# MotorController.net
KiCad netlist of a schematic drawn in Altium Designer
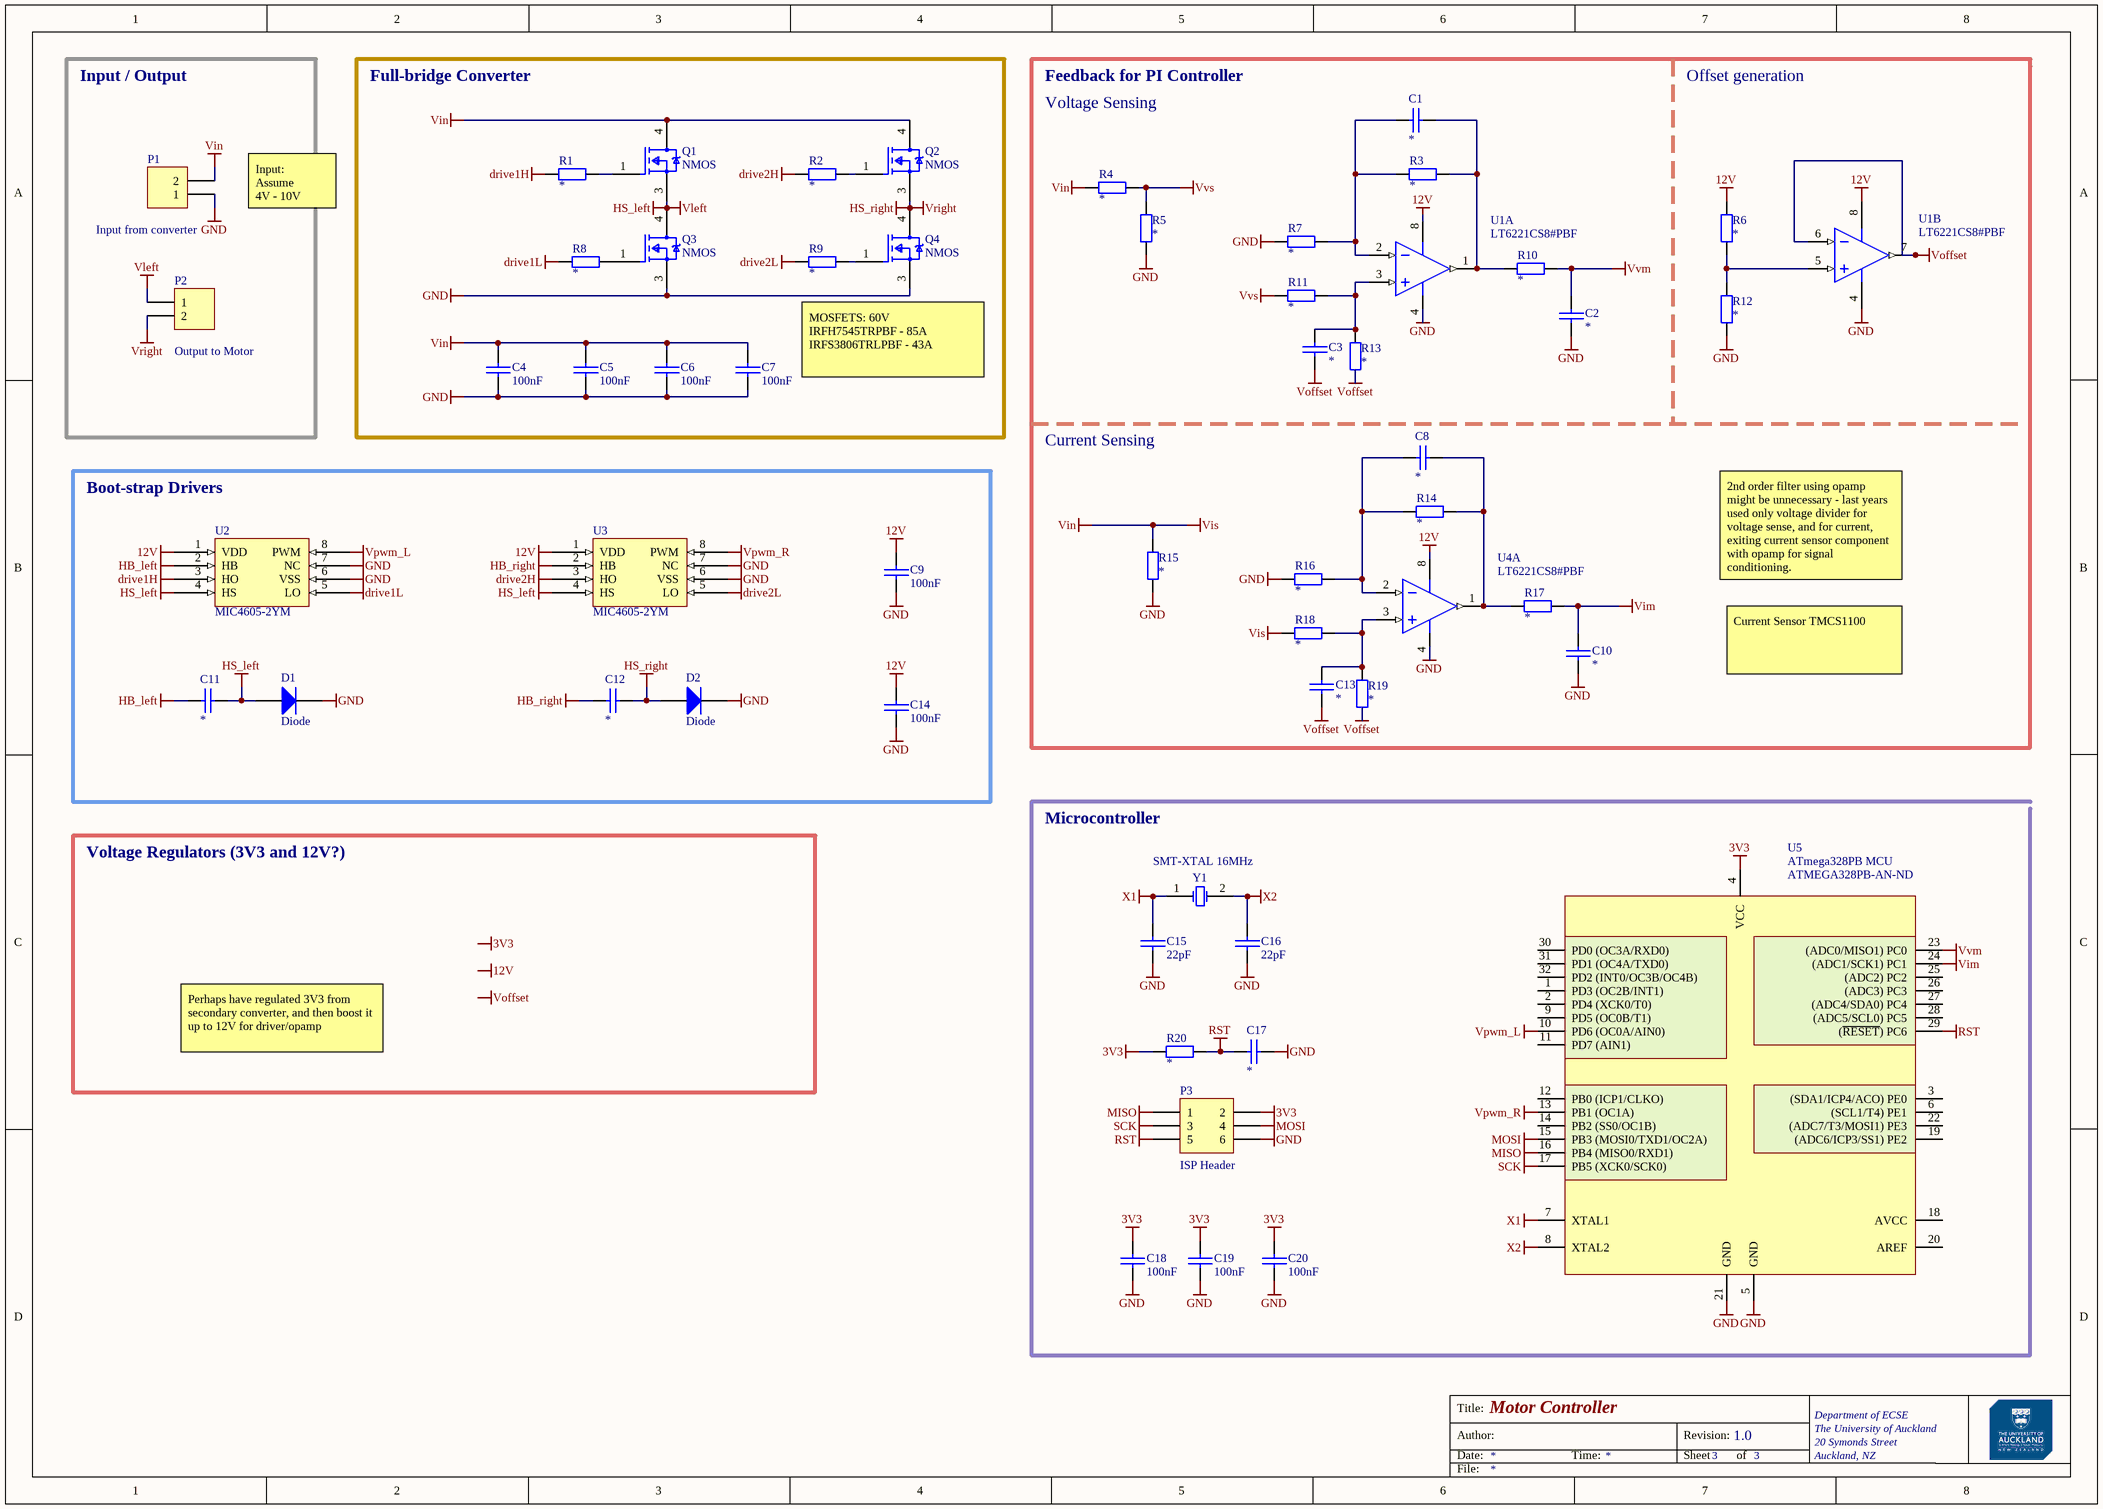
[diagram p0: MotorController.SchDoc]

(export (version "E")
  (design (tool "Eeschema 10.0.6"))
  (components
    (comp (ref "C1")
      (value "*")
      (footprint "0805 CAP")
      (description "SMT ceramic capacitor 0805 size")
      (libsource (lib "EE209_Library") (part "CerCap_SMT_0805"))
    )
    (comp (ref "C2")
      (value "*")
      (footprint "0805 CAP")
      (description "SMT ceramic capacitor 0805 size")
      (libsource (lib "EE209_Library") (part "CerCap_SMT_0805"))
    )
    (comp (ref "C3")
      (value "*")
      (footprint "0805 CAP")
      (description "SMT ceramic capacitor 0805 size")
      (libsource (lib "EE209_Library") (part "CerCap_SMT_0805"))
    )
    (comp (ref "C4")
      (value "100nF")
      (footprint "0805 CAP")
      (description "SMT ceramic capacitor 0805 size")
      (libsource (lib "EE209_Library") (part "CerCap_SMT_0805"))
    )
    (comp (ref "C5")
      (value "100nF")
      (footprint "0805 CAP")
      (description "SMT ceramic capacitor 0805 size")
      (libsource (lib "EE209_Library") (part "CerCap_SMT_0805"))
    )
    (comp (ref "C6")
      (value "100nF")
      (footprint "0805 CAP")
      (description "SMT ceramic capacitor 0805 size")
      (libsource (lib "EE209_Library") (part "CerCap_SMT_0805"))
    )
    (comp (ref "C7")
      (value "100nF")
      (footprint "0805 CAP")
      (description "SMT ceramic capacitor 0805 size")
      (libsource (lib "EE209_Library") (part "CerCap_SMT_0805"))
    )
    (comp (ref "C8")
      (value "*")
      (footprint "0805 CAP")
      (description "SMT ceramic capacitor 0805 size")
      (libsource (lib "EE209_Library") (part "CerCap_SMT_0805"))
    )
    (comp (ref "C9")
      (value "100nF")
      (footprint "0805 CAP")
      (description "SMT ceramic capacitor 0805 size")
      (libsource (lib "EE209_Library") (part "CerCap_SMT_0805"))
    )
    (comp (ref "C10")
      (value "*")
      (footprint "0805 CAP")
      (description "SMT ceramic capacitor 0805 size")
      (libsource (lib "EE209_Library") (part "CerCap_SMT_0805"))
    )
    (comp (ref "C11")
      (value "*")
      (footprint "0805 CAP")
      (description "SMT ceramic capacitor 0805 size")
      (libsource (lib "EE209_Library") (part "CerCap_SMT_0805"))
    )
    (comp (ref "C12")
      (value "*")
      (footprint "0805 CAP")
      (description "SMT ceramic capacitor 0805 size")
      (libsource (lib "EE209_Library") (part "CerCap_SMT_0805"))
    )
    (comp (ref "C13")
      (value "*")
      (footprint "0805 CAP")
      (description "SMT ceramic capacitor 0805 size")
      (libsource (lib "EE209_Library") (part "CerCap_SMT_0805"))
    )
    (comp (ref "C14")
      (value "100nF")
      (footprint "0805 CAP")
      (description "SMT ceramic capacitor 0805 size")
      (libsource (lib "EE209_Library") (part "CerCap_SMT_0805"))
    )
    (comp (ref "C15")
      (value "22pF")
      (footprint "0805 CAP")
      (description "SMT ceramic capacitor 0805 size")
      (libsource (lib "EE209_Library") (part "CerCap_SMT_0805"))
    )
    (comp (ref "C16")
      (value "22pF")
      (footprint "0805 CAP")
      (description "SMT ceramic capacitor 0805 size")
      (libsource (lib "EE209_Library") (part "CerCap_SMT_0805"))
    )
    (comp (ref "C17")
      (value "*")
      (footprint "0805 CAP")
      (description "SMT ceramic capacitor 0805 size")
      (libsource (lib "EE209_Library") (part "CerCap_SMT_0805"))
    )
    (comp (ref "C18")
      (value "100nF")
      (footprint "0805 CAP")
      (description "SMT ceramic capacitor 0805 size")
      (libsource (lib "EE209_Library") (part "CerCap_SMT_0805"))
    )
    (comp (ref "C19")
      (value "100nF")
      (footprint "0805 CAP")
      (description "SMT ceramic capacitor 0805 size")
      (libsource (lib "EE209_Library") (part "CerCap_SMT_0805"))
    )
    (comp (ref "C20")
      (value "100nF")
      (footprint "0805 CAP")
      (description "SMT ceramic capacitor 0805 size")
      (libsource (lib "EE209_Library") (part "CerCap_SMT_0805"))
    )
    (comp (ref "D1")
      (value "Diode")
      (footprint "SMC")
      (description "Default Diode")
      (fields (field (name "PUBLISHER") "Altium Limited"))
      (libsource (lib "Miscellaneous Devices") (part "Diode"))
    )
    (comp (ref "D2")
      (value "Diode")
      (footprint "SMC")
      (description "Default Diode")
      (fields (field (name "PUBLISHER") "Altium Limited"))
      (libsource (lib "Miscellaneous Devices") (part "Diode"))
    )
    (comp (ref "P1")
      (value "Input from converter")
      (footprint "HDR1X2H")
      (description "Header, 2-Pin, Right Angle")
      (fields (field (name "PUBLISHER") "Altium Limited"))
      (libsource (lib "") (part "Header 2H_1"))
    )
    (comp (ref "P2")
      (value "Output to Motor")
      (footprint "HDR1X2H")
      (description "Header, 2-Pin, Right Angle")
      (fields (field (name "PUBLISHER") "Altium Limited"))
      (libsource (lib "Miscellaneous Connectors") (part "Header 2H"))
    )
    (comp (ref "P3")
      (value "ISP Header")
      (footprint "HDR2X3")
      (description "Header, 3-Pin, Dual row")
      (fields (field (name "PUBLISHER") "Altium Limited"))
      (libsource (lib "Miscellaneous Connectors") (part "Header 3X2"))
    )
    (comp (ref "Q1")
      (value "NMOS")
      (footprint "IRFS3806TRLPBFCT-ND")
      (description "Single N-Channel 60V 15.8 mOhm 22 nC HEXFET® Power Mosfet - D2PAK")
      (fields
        (field (name "MANUFACTURER") "Infineon")
        (field (name "MANUFACTURER PART NUMBER") "IRFS3806TRLPBF")
      )
      (libsource (lib "SummerWorkshop") (part "NMOS"))
    )
    (comp (ref "Q2")
      (value "NMOS")
      (footprint "IRFS3806TRLPBFCT-ND")
      (description "Single N-Channel 60V 15.8 mOhm 22 nC HEXFET® Power Mosfet - D2PAK")
      (fields
        (field (name "MANUFACTURER") "Infineon")
        (field (name "MANUFACTURER PART NUMBER") "IRFS3806TRLPBF")
      )
      (libsource (lib "SummerWorkshop") (part "NMOS"))
    )
    (comp (ref "Q3")
      (value "NMOS")
      (footprint "IRFS3806TRLPBFCT-ND")
      (description "Single N-Channel 60V 15.8 mOhm 22 nC HEXFET® Power Mosfet - D2PAK")
      (fields
        (field (name "MANUFACTURER") "Infineon")
        (field (name "MANUFACTURER PART NUMBER") "IRFS3806TRLPBF")
      )
      (libsource (lib "SummerWorkshop") (part "NMOS"))
    )
    (comp (ref "Q4")
      (value "NMOS")
      (footprint "IRFS3806TRLPBFCT-ND")
      (description "Single N-Channel 60V 15.8 mOhm 22 nC HEXFET® Power Mosfet - D2PAK")
      (fields
        (field (name "MANUFACTURER") "Infineon")
        (field (name "MANUFACTURER PART NUMBER") "IRFS3806TRLPBF")
      )
      (libsource (lib "SummerWorkshop") (part "NMOS"))
    )
    (comp (ref "R1")
      (value "*")
      (footprint "0805 RES")
      (description "0805 resistor")
      (fields (field (name "PUBLISHER") "Altium Limited"))
      (libsource (lib "EE209_Library") (part "Res_SMT_0805"))
    )
    (comp (ref "R2")
      (value "*")
      (footprint "0805 RES")
      (description "0805 resistor")
      (fields (field (name "PUBLISHER") "Altium Limited"))
      (libsource (lib "EE209_Library") (part "Res_SMT_0805"))
    )
    (comp (ref "R3")
      (value "*")
      (footprint "0805 RES")
      (description "0805 resistor")
      (fields (field (name "PUBLISHER") "Altium Limited"))
      (libsource (lib "") (part "Res_SMT_0805_2"))
    )
    (comp (ref "R4")
      (value "*")
      (footprint "0805 RES")
      (description "0805 resistor")
      (fields (field (name "PUBLISHER") "Altium Limited"))
      (libsource (lib "") (part "Res_SMT_0805_2"))
    )
    (comp (ref "R5")
      (value "*")
      (footprint "0805 RES")
      (description "0805 resistor")
      (fields (field (name "PUBLISHER") "Altium Limited"))
      (libsource (lib "") (part "Res_SMT_0805_3"))
    )
    (comp (ref "R6")
      (value "*")
      (footprint "0805 RES")
      (description "0805 resistor")
      (fields (field (name "PUBLISHER") "Altium Limited"))
      (libsource (lib "") (part "Res_SMT_0805_1"))
    )
    (comp (ref "R7")
      (value "*")
      (footprint "0805 RES")
      (description "0805 resistor")
      (fields (field (name "PUBLISHER") "Altium Limited"))
      (libsource (lib "EE209_Library") (part "Res_SMT_0805"))
    )
    (comp (ref "R8")
      (value "*")
      (footprint "0805 RES")
      (description "0805 resistor")
      (fields (field (name "PUBLISHER") "Altium Limited"))
      (libsource (lib "EE209_Library") (part "Res_SMT_0805"))
    )
    (comp (ref "R9")
      (value "*")
      (footprint "0805 RES")
      (description "0805 resistor")
      (fields (field (name "PUBLISHER") "Altium Limited"))
      (libsource (lib "EE209_Library") (part "Res_SMT_0805"))
    )
    (comp (ref "R10")
      (value "*")
      (footprint "0805 RES")
      (description "0805 resistor")
      (fields (field (name "PUBLISHER") "Altium Limited"))
      (libsource (lib "") (part "Res_SMT_0805_2"))
    )
    (comp (ref "R11")
      (value "*")
      (footprint "0805 RES")
      (description "0805 resistor")
      (fields (field (name "PUBLISHER") "Altium Limited"))
      (libsource (lib "EE209_Library") (part "Res_SMT_0805"))
    )
    (comp (ref "R12")
      (value "*")
      (footprint "0805 RES")
      (description "0805 resistor")
      (fields (field (name "PUBLISHER") "Altium Limited"))
      (libsource (lib "") (part "Res_SMT_0805_1"))
    )
    (comp (ref "R13")
      (value "*")
      (footprint "0805 RES")
      (description "0805 resistor")
      (fields (field (name "PUBLISHER") "Altium Limited"))
      (libsource (lib "") (part "Res_SMT_0805_1"))
    )
    (comp (ref "R14")
      (value "*")
      (footprint "0805 RES")
      (description "0805 resistor")
      (fields (field (name "PUBLISHER") "Altium Limited"))
      (libsource (lib "") (part "Res_SMT_0805_2"))
    )
    (comp (ref "R15")
      (value "*")
      (footprint "0805 RES")
      (description "0805 resistor")
      (fields (field (name "PUBLISHER") "Altium Limited"))
      (libsource (lib "") (part "Res_SMT_0805_3"))
    )
    (comp (ref "R16")
      (value "*")
      (footprint "0805 RES")
      (description "0805 resistor")
      (fields (field (name "PUBLISHER") "Altium Limited"))
      (libsource (lib "EE209_Library") (part "Res_SMT_0805"))
    )
    (comp (ref "R17")
      (value "*")
      (footprint "0805 RES")
      (description "0805 resistor")
      (fields (field (name "PUBLISHER") "Altium Limited"))
      (libsource (lib "") (part "Res_SMT_0805_2"))
    )
    (comp (ref "R18")
      (value "*")
      (footprint "0805 RES")
      (description "0805 resistor")
      (fields (field (name "PUBLISHER") "Altium Limited"))
      (libsource (lib "EE209_Library") (part "Res_SMT_0805"))
    )
    (comp (ref "R19")
      (value "*")
      (footprint "0805 RES")
      (description "0805 resistor")
      (fields (field (name "PUBLISHER") "Altium Limited"))
      (libsource (lib "") (part "Res_SMT_0805_1"))
    )
    (comp (ref "R20")
      (value "*")
      (footprint "0805 RES")
      (description "0805 resistor")
      (fields (field (name "PUBLISHER") "Altium Limited"))
      (libsource (lib "") (part "Res_SMT_0805_2"))
    )
    (comp (ref "U1")
      (value "LT6221CS8#PBF")
      (footprint "LT-S8-8_N")
      (fields
        (field (name "LINEAR TECHNOLOGY PART NUMBER") "LT6221")
        (field (name "MANUFACTURER") "Linear Technology")
      )
      (libsource (lib "Altium Content Vault") (part "LT-LT6221-S8-8"))
    )
    (comp (ref "U2")
      (value "MIC4605-2YM")
      (description "Driver 1A 2-OUT High and Low Side Half Brdg Non-Inv 8-Pin SOIC N Tube")
      (fields
        (field (name "MANUFACTURER") "Microchip")
        (field (name "MANUFACTURER PART NUMBER") "MIC4605-2YM-T5")
      )
      (libsource (lib "SummerWorkshop") (part "MIC4605-2YM"))
    )
    (comp (ref "U3")
      (value "MIC4605-2YM")
      (description "Driver 1A 2-OUT High and Low Side Half Brdg Non-Inv 8-Pin SOIC N Tube")
      (fields
        (field (name "MANUFACTURER") "Microchip")
        (field (name "MANUFACTURER PART NUMBER") "MIC4605-2YM-T5")
      )
      (libsource (lib "SummerWorkshop") (part "MIC4605-2YM"))
    )
    (comp (ref "U4")
      (value "LT6221CS8#PBF")
      (footprint "LT-S8-8_N")
      (fields
        (field (name "LINEAR TECHNOLOGY PART NUMBER") "LT6221")
        (field (name "MANUFACTURER") "Linear Technology")
      )
      (libsource (lib "Altium Content Vault") (part "LT-LT6221-S8-8"))
    )
    (comp (ref "U5")
      (value "ATmega328PB MCU")
      (footprint "32 - TQFP")
      (description "IC MCU 8BIT 32KB FLASH 32TQFP")
      (fields
        (field (name "MANUFACTURER") "Atmel")
        (field (name "MANUFACTURER PART NUMBER") "ATMEGA328PB-AN")
        (field (name "SUPPLIER PART NUMBER 1") "ATMEGA328PB-AN-ND")
      )
      (libsource (lib "EE209_Library") (part "ATmega328PB_SMT_TQFP32"))
    )
    (comp (ref "Y1")
      (value "SMT-XTAL 16MHz")
      (footprint "HC49-US")
      (description "9C-16.000MAAJ-T crystal 16.0000MHZ 18PF SMD")
      (fields
        (field (name "MANUFACTURER") "TXC CORPORATION")
        (field (name "MANUFACTURER PART NUMBER") "9C-16.000MAAJ-T")
      )
      (libsource (lib "EE209_Library") (part "TXC9C-16_XTAL_SMT"))
    )
  )
  (nets
    (net (code "1") (name "3V3") (class "Default")
      (node (ref "C18") (pin "1") (pinfunction "1_1") (pintype "passive"))
      (node (ref "C19") (pin "1") (pinfunction "1_1") (pintype "passive"))
      (node (ref "C20") (pin "1") (pinfunction "1_1") (pintype "passive"))
      (node (ref "P3") (pin "2") (pinfunction "2_2") (pintype "passive"))
      (node (ref "R20") (pin "2") (pinfunction "2_2") (pintype "passive"))
      (node (ref "U5") (pin "4") (pinfunction "VCC_4") (pintype "passive"))
    )
    (net (code "2") (name "12V") (class "Default")
      (node (ref "C14") (pin "2") (pinfunction "2_2") (pintype "passive"))
      (node (ref "C9") (pin "2") (pinfunction "2_2") (pintype "passive"))
      (node (ref "R6") (pin "2") (pinfunction "2_2") (pintype "passive"))
      (node (ref "U1") (pin "8") (pinfunction "VS+_8") (pintype "power_in"))
      (node (ref "U2") (pin "1") (pinfunction "VDD_1") (pintype "input"))
      (node (ref "U3") (pin "1") (pinfunction "VDD_1") (pintype "input"))
      (node (ref "U4") (pin "8") (pinfunction "VS+_8") (pintype "power_in"))
    )
    (net (code "3") (name "GND") (class "Default")
      (node (ref "C10") (pin "1") (pinfunction "1_1") (pintype "passive"))
      (node (ref "C14") (pin "1") (pinfunction "1_1") (pintype "passive"))
      (node (ref "C15") (pin "2") (pinfunction "2_2") (pintype "passive"))
      (node (ref "C16") (pin "2") (pinfunction "2_2") (pintype "passive"))
      (node (ref "C17") (pin "2") (pinfunction "2_2") (pintype "passive"))
      (node (ref "C18") (pin "2") (pinfunction "2_2") (pintype "passive"))
      (node (ref "C19") (pin "2") (pinfunction "2_2") (pintype "passive"))
      (node (ref "C2") (pin "1") (pinfunction "1_1") (pintype "passive"))
      (node (ref "C20") (pin "2") (pinfunction "2_2") (pintype "passive"))
      (node (ref "C4") (pin "1") (pinfunction "1_1") (pintype "passive"))
      (node (ref "C5") (pin "1") (pinfunction "1_1") (pintype "passive"))
      (node (ref "C6") (pin "1") (pinfunction "1_1") (pintype "passive"))
      (node (ref "C7") (pin "1") (pinfunction "1_1") (pintype "passive"))
      (node (ref "C9") (pin "1") (pinfunction "1_1") (pintype "passive"))
      (node (ref "D1") (pin "2") (pinfunction "K_2") (pintype "passive"))
      (node (ref "D2") (pin "2") (pinfunction "K_2") (pintype "passive"))
      (node (ref "P1") (pin "1") (pinfunction "1_1") (pintype "passive"))
      (node (ref "P3") (pin "6") (pinfunction "6_6") (pintype "passive"))
      (node (ref "Q3") (pin "3") (pinfunction "S_3") (pintype "passive"))
      (node (ref "Q4") (pin "3") (pinfunction "S_3") (pintype "passive"))
      (node (ref "R12") (pin "1") (pinfunction "1_1") (pintype "passive"))
      (node (ref "R15") (pin "2") (pinfunction "2_2") (pintype "passive"))
      (node (ref "R16") (pin "1") (pinfunction "1_1") (pintype "passive"))
      (node (ref "R5") (pin "2") (pinfunction "2_2") (pintype "passive"))
      (node (ref "R7") (pin "1") (pinfunction "1_1") (pintype "passive"))
      (node (ref "U1") (pin "4") (pinfunction "VS-_4") (pintype "power_in"))
      (node (ref "U2") (pin "6") (pinfunction "VSS_6") (pintype "input"))
      (node (ref "U2") (pin "7") (pinfunction "NC_7") (pintype "input"))
      (node (ref "U3") (pin "6") (pinfunction "VSS_6") (pintype "input"))
      (node (ref "U3") (pin "7") (pinfunction "NC_7") (pintype "input"))
      (node (ref "U4") (pin "4") (pinfunction "VS-_4") (pintype "power_in"))
      (node (ref "U5") (pin "21") (pinfunction "GND_21") (pintype "passive"))
      (node (ref "U5") (pin "5") (pinfunction "GND_5") (pintype "passive"))
    )
    (net (code "4") (name "HB_left") (class "Default")
      (node (ref "C11") (pin "1") (pinfunction "1_1") (pintype "passive"))
      (node (ref "U2") (pin "2") (pinfunction "HB_2") (pintype "input"))
    )
    (net (code "5") (name "HB_right") (class "Default")
      (node (ref "C12") (pin "1") (pinfunction "1_1") (pintype "passive"))
      (node (ref "U3") (pin "2") (pinfunction "HB_2") (pintype "input"))
    )
    (net (code "6") (name "HS_left") (class "Default")
      (node (ref "C11") (pin "2") (pinfunction "2_2") (pintype "passive"))
      (node (ref "D1") (pin "1") (pinfunction "A_1") (pintype "passive"))
      (node (ref "P2") (pin "1") (pinfunction "1_1") (pintype "passive"))
      (node (ref "Q1") (pin "3") (pinfunction "S_3") (pintype "passive"))
      (node (ref "Q3") (pin "4") (pinfunction "D_4") (pintype "passive"))
      (node (ref "U2") (pin "4") (pinfunction "HS_4") (pintype "input"))
      (node (ref "U3") (pin "4") (pinfunction "HS_4") (pintype "input"))
    )
    (net (code "7") (name "HS_right") (class "Default")
      (node (ref "C12") (pin "2") (pinfunction "2_2") (pintype "passive"))
      (node (ref "D2") (pin "1") (pinfunction "A_1") (pintype "passive"))
      (node (ref "P2") (pin "2") (pinfunction "2_2") (pintype "passive"))
      (node (ref "Q2") (pin "3") (pinfunction "S_3") (pintype "passive"))
      (node (ref "Q4") (pin "4") (pinfunction "D_4") (pintype "passive"))
    )
    (net (code "8") (name "MISO") (class "Default")
      (node (ref "P3") (pin "1") (pinfunction "1_1") (pintype "passive"))
      (node (ref "U5") (pin "16") (pinfunction "PB4_(MISO0/RXD1)_16") (pintype "passive"))
    )
    (net (code "9") (name "MOSI") (class "Default")
      (node (ref "P3") (pin "4") (pinfunction "4_4") (pintype "passive"))
      (node (ref "U5") (pin "15") (pinfunction "PB3_(MOSI0/TXD1/OC2A)_15") (pintype "passive"))
    )
    (net (code "10") (name "Net-(Q1-G)") (class "Default")
      (node (ref "Q1") (pin "1") (pinfunction "G_1") (pintype "passive"))
      (node (ref "R1") (pin "2") (pinfunction "2_2") (pintype "passive"))
    )
    (net (code "11") (name "Net-(Q2-G)") (class "Default")
      (node (ref "Q2") (pin "1") (pinfunction "G_1") (pintype "passive"))
      (node (ref "R2") (pin "2") (pinfunction "2_2") (pintype "passive"))
    )
    (net (code "12") (name "Net-(Q3-G)") (class "Default")
      (node (ref "Q3") (pin "1") (pinfunction "G_1") (pintype "passive"))
      (node (ref "R8") (pin "2") (pinfunction "2_2") (pintype "passive"))
    )
    (net (code "13") (name "Net-(Q4-G)") (class "Default")
      (node (ref "Q4") (pin "1") (pinfunction "G_1") (pintype "passive"))
      (node (ref "R9") (pin "2") (pinfunction "2_2") (pintype "passive"))
    )
    (net (code "14") (name "Net-(U1A-+IN_A)") (class "Default")
      (node (ref "C3") (pin "2") (pinfunction "2_2") (pintype "passive"))
      (node (ref "R11") (pin "2") (pinfunction "2_2") (pintype "passive"))
      (node (ref "R13") (pin "2") (pinfunction "2_2") (pintype "passive"))
      (node (ref "U1") (pin "3") (pinfunction "+IN_A_3") (pintype "input"))
    )
    (net (code "15") (name "Net-(U1A--IN_A)") (class "Default")
      (node (ref "C1") (pin "1") (pinfunction "1_1") (pintype "passive"))
      (node (ref "R3") (pin "2") (pinfunction "2_2") (pintype "passive"))
      (node (ref "R7") (pin "2") (pinfunction "2_2") (pintype "passive"))
      (node (ref "U1") (pin "2") (pinfunction "-IN_A_2") (pintype "input"))
    )
    (net (code "16") (name "Net-(U1A-OUT_A)") (class "Default")
      (node (ref "C1") (pin "2") (pinfunction "2_2") (pintype "passive"))
      (node (ref "R10") (pin "2") (pinfunction "2_2") (pintype "passive"))
      (node (ref "R3") (pin "1") (pinfunction "1_1") (pintype "passive"))
      (node (ref "U1") (pin "1") (pinfunction "OUT_A_1") (pintype "output"))
    )
    (net (code "17") (name "Net-(U1B-+IN_B)") (class "Default")
      (node (ref "R12") (pin "2") (pinfunction "2_2") (pintype "passive"))
      (node (ref "R6") (pin "1") (pinfunction "1_1") (pintype "passive"))
      (node (ref "U1") (pin "5") (pinfunction "+IN_B_5") (pintype "input"))
    )
    (net (code "18") (name "Net-(U4A-+IN_A)") (class "Default")
      (node (ref "C13") (pin "2") (pinfunction "2_2") (pintype "passive"))
      (node (ref "R18") (pin "2") (pinfunction "2_2") (pintype "passive"))
      (node (ref "R19") (pin "2") (pinfunction "2_2") (pintype "passive"))
      (node (ref "U4") (pin "3") (pinfunction "+IN_A_3") (pintype "input"))
    )
    (net (code "19") (name "Net-(U4A--IN_A)") (class "Default")
      (node (ref "C8") (pin "1") (pinfunction "1_1") (pintype "passive"))
      (node (ref "R14") (pin "2") (pinfunction "2_2") (pintype "passive"))
      (node (ref "R16") (pin "2") (pinfunction "2_2") (pintype "passive"))
      (node (ref "U4") (pin "2") (pinfunction "-IN_A_2") (pintype "input"))
    )
    (net (code "20") (name "Net-(U4A-OUT_A)") (class "Default")
      (node (ref "C8") (pin "2") (pinfunction "2_2") (pintype "passive"))
      (node (ref "R14") (pin "1") (pinfunction "1_1") (pintype "passive"))
      (node (ref "R17") (pin "2") (pinfunction "2_2") (pintype "passive"))
      (node (ref "U4") (pin "1") (pinfunction "OUT_A_1") (pintype "output"))
    )
    (net (code "21") (name "RST") (class "Default")
      (node (ref "C17") (pin "1") (pinfunction "1_1") (pintype "passive"))
      (node (ref "P3") (pin "5") (pinfunction "5_5") (pintype "passive"))
      (node (ref "R20") (pin "1") (pinfunction "1_1") (pintype "passive"))
      (node (ref "U5") (pin "29") (pinfunction "(~{RESET})_PC6_29") (pintype "passive"))
    )
    (net (code "22") (name "SCK") (class "Default")
      (node (ref "P3") (pin "3") (pinfunction "3_3") (pintype "passive"))
      (node (ref "U5") (pin "17") (pinfunction "PB5_(XCK0/SCK0)_17") (pintype "passive"))
    )
    (net (code "23") (name "Vim") (class "Default")
      (node (ref "C10") (pin "2") (pinfunction "2_2") (pintype "passive"))
      (node (ref "R17") (pin "1") (pinfunction "1_1") (pintype "passive"))
      (node (ref "U5") (pin "24") (pinfunction "(ADC1/SCK1)_PC1_24") (pintype "passive"))
    )
    (net (code "24") (name "Vin") (class "Default")
      (node (ref "C4") (pin "2") (pinfunction "2_2") (pintype "passive"))
      (node (ref "C5") (pin "2") (pinfunction "2_2") (pintype "passive"))
      (node (ref "C6") (pin "2") (pinfunction "2_2") (pintype "passive"))
      (node (ref "C7") (pin "2") (pinfunction "2_2") (pintype "passive"))
      (node (ref "P1") (pin "2") (pinfunction "2_2") (pintype "passive"))
      (node (ref "Q1") (pin "4") (pinfunction "D_4") (pintype "passive"))
      (node (ref "Q2") (pin "4") (pinfunction "D_4") (pintype "passive"))
      (node (ref "R15") (pin "1") (pinfunction "1_1") (pintype "passive"))
      (node (ref "R18") (pin "1") (pinfunction "1_1") (pintype "passive"))
      (node (ref "R4") (pin "2") (pinfunction "2_2") (pintype "passive"))
    )
    (net (code "25") (name "Voffset") (class "Default")
      (node (ref "C13") (pin "1") (pinfunction "1_1") (pintype "passive"))
      (node (ref "C3") (pin "1") (pinfunction "1_1") (pintype "passive"))
      (node (ref "R13") (pin "1") (pinfunction "1_1") (pintype "passive"))
      (node (ref "R19") (pin "1") (pinfunction "1_1") (pintype "passive"))
      (node (ref "U1") (pin "6") (pinfunction "-IN_B_6") (pintype "input"))
      (node (ref "U1") (pin "7") (pinfunction "OUT_B_7") (pintype "output"))
    )
    (net (code "26") (name "Vpwm_L") (class "Default")
      (node (ref "U2") (pin "8") (pinfunction "PWM_8") (pintype "input"))
      (node (ref "U5") (pin "10") (pinfunction "PD6_(OC0A/AIN0)_10") (pintype "passive"))
    )
    (net (code "27") (name "Vpwm_R") (class "Default")
      (node (ref "U3") (pin "8") (pinfunction "PWM_8") (pintype "input"))
      (node (ref "U5") (pin "13") (pinfunction "PB1_(OC1A)_13") (pintype "passive"))
    )
    (net (code "28") (name "Vvm") (class "Default")
      (node (ref "C2") (pin "2") (pinfunction "2_2") (pintype "passive"))
      (node (ref "R10") (pin "1") (pinfunction "1_1") (pintype "passive"))
      (node (ref "U5") (pin "23") (pinfunction "(ADC0/MISO1)_PC0_23") (pintype "passive"))
    )
    (net (code "29") (name "Vvs") (class "Default")
      (node (ref "R11") (pin "1") (pinfunction "1_1") (pintype "passive"))
      (node (ref "R4") (pin "1") (pinfunction "1_1") (pintype "passive"))
      (node (ref "R5") (pin "1") (pinfunction "1_1") (pintype "passive"))
    )
    (net (code "30") (name "X1") (class "Default")
      (node (ref "C15") (pin "1") (pinfunction "1_1") (pintype "passive"))
      (node (ref "U5") (pin "7") (pinfunction "XTAL1_7") (pintype "passive"))
      (node (ref "Y1") (pin "1") (pinfunction "OSC1_1") (pintype "passive"))
    )
    (net (code "31") (name "X2") (class "Default")
      (node (ref "C16") (pin "1") (pinfunction "1_1") (pintype "passive"))
      (node (ref "U5") (pin "8") (pinfunction "XTAL2_8") (pintype "passive"))
      (node (ref "Y1") (pin "2") (pinfunction "OSC2_2") (pintype "passive"))
    )
    (net (code "32") (name "drive1H") (class "Default")
      (node (ref "R1") (pin "1") (pinfunction "1_1") (pintype "passive"))
      (node (ref "U2") (pin "3") (pinfunction "HO_3") (pintype "input"))
    )
    (net (code "33") (name "drive1L") (class "Default")
      (node (ref "R8") (pin "1") (pinfunction "1_1") (pintype "passive"))
      (node (ref "U2") (pin "5") (pinfunction "LO_5") (pintype "input"))
    )
    (net (code "34") (name "drive2H") (class "Default")
      (node (ref "R2") (pin "1") (pinfunction "1_1") (pintype "passive"))
      (node (ref "U3") (pin "3") (pinfunction "HO_3") (pintype "input"))
    )
    (net (code "35") (name "drive2L") (class "Default")
      (node (ref "R9") (pin "1") (pinfunction "1_1") (pintype "passive"))
      (node (ref "U3") (pin "5") (pinfunction "LO_5") (pintype "input"))
    )
    (net (code "36") (name "unconnected-(U5-(ADC2)_PC2-Pad25)") (class "Default")
      (node (ref "U5") (pin "25") (pinfunction "(ADC2)_PC2_25") (pintype "passive"))
    )
    (net (code "37") (name "unconnected-(U5-(ADC3)_PC3-Pad26)") (class "Default")
      (node (ref "U5") (pin "26") (pinfunction "(ADC3)_PC3_26") (pintype "passive"))
    )
    (net (code "38") (name "unconnected-(U5-(ADC4{slash}SDA0)_PC4-Pad27)") (class "Default")
      (node (ref "U5") (pin "27") (pinfunction "(ADC4/SDA0)_PC4_27") (pintype "passive"))
    )
    (net (code "39") (name "unconnected-(U5-(ADC5{slash}SCL0)_PC5-Pad28)") (class "Default")
      (node (ref "U5") (pin "28") (pinfunction "(ADC5/SCL0)_PC5_28") (pintype "passive"))
    )
    (net (code "40") (name "unconnected-(U5-(ADC6{slash}ICP3{slash}SS1)_PE2-Pad19)") (class "Default")
      (node (ref "U5") (pin "19") (pinfunction "(ADC6/ICP3/SS1)_PE2_19") (pintype "passive"))
    )
    (net (code "41") (name "unconnected-(U5-(ADC7{slash}T3{slash}MOSI1)_PE3-Pad22)") (class "Default")
      (node (ref "U5") (pin "22") (pinfunction "(ADC7/T3/MOSI1)_PE3_22") (pintype "passive"))
    )
    (net (code "42") (name "unconnected-(U5-(SCL1{slash}T4)_PE1-Pad6)") (class "Default")
      (node (ref "U5") (pin "6") (pinfunction "(SCL1/T4)_PE1_6") (pintype "passive"))
    )
    (net (code "43") (name "unconnected-(U5-(SDA1{slash}ICP4{slash}ACO)_PE0-Pad3)") (class "Default")
      (node (ref "U5") (pin "3") (pinfunction "(SDA1/ICP4/ACO)_PE0_3") (pintype "passive"))
    )
    (net (code "44") (name "unconnected-(U5-AREF-Pad20)") (class "Default")
      (node (ref "U5") (pin "20") (pinfunction "AREF_20") (pintype "passive"))
    )
    (net (code "45") (name "unconnected-(U5-AVCC-Pad18)") (class "Default")
      (node (ref "U5") (pin "18") (pinfunction "AVCC_18") (pintype "passive"))
    )
    (net (code "46") (name "unconnected-(U5-PB0_(ICP1{slash}CLKO)-Pad12)") (class "Default")
      (node (ref "U5") (pin "12") (pinfunction "PB0_(ICP1/CLKO)_12") (pintype "passive"))
    )
    (net (code "47") (name "unconnected-(U5-PB2_(SS0{slash}OC1B)-Pad14)") (class "Default")
      (node (ref "U5") (pin "14") (pinfunction "PB2_(SS0/OC1B)_14") (pintype "passive"))
    )
    (net (code "48") (name "unconnected-(U5-PD0_(OC3A{slash}RXD0)-Pad30)") (class "Default")
      (node (ref "U5") (pin "30") (pinfunction "PD0_(OC3A/RXD0)_30") (pintype "passive"))
    )
    (net (code "49") (name "unconnected-(U5-PD1_(OC4A{slash}TXD0)-Pad31)") (class "Default")
      (node (ref "U5") (pin "31") (pinfunction "PD1_(OC4A/TXD0)_31") (pintype "passive"))
    )
    (net (code "50") (name "unconnected-(U5-PD2_(INT0{slash}OC3B{slash}OC4B)-Pad32)") (class "Default")
      (node (ref "U5") (pin "32") (pinfunction "PD2_(INT0/OC3B/OC4B)_32") (pintype "passive"))
    )
    (net (code "51") (name "unconnected-(U5-PD3_(OC2B{slash}INT1)-Pad1)") (class "Default")
      (node (ref "U5") (pin "1") (pinfunction "PD3_(OC2B/INT1)_1") (pintype "passive"))
    )
    (net (code "52") (name "unconnected-(U5-PD4_(XCK0{slash}T0)-Pad2)") (class "Default")
      (node (ref "U5") (pin "2") (pinfunction "PD4_(XCK0/T0)_2") (pintype "passive"))
    )
    (net (code "53") (name "unconnected-(U5-PD5_(OC0B{slash}T1)-Pad9)") (class "Default")
      (node (ref "U5") (pin "9") (pinfunction "PD5_(OC0B/T1)_9") (pintype "passive"))
    )
    (net (code "54") (name "unconnected-(U5-PD7_(AIN1)-Pad11)") (class "Default")
      (node (ref "U5") (pin "11") (pinfunction "PD7_(AIN1)_11") (pintype "passive"))
    )
  )
)
